# WiFi.net
KiCad netlist of a schematic drawn in EAGLE
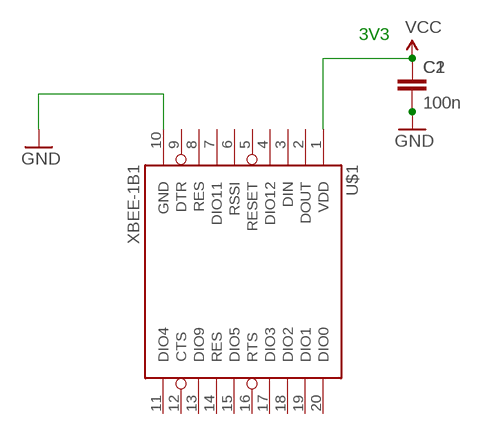
[diagram p0: schematic, sheet 1]

(export (version "E")
  (design (tool "Eeschema 10.0.6"))
  (components
    (comp (ref "C1")
      (value "CAPKIT")
      (footprint "eagle-import:CAP-PTH-SMALL-KIT")
      (libsource (lib "eagle-import") (part "CAPKIT"))
    )
    (comp (ref "C2")
      (value "100n")
      (footprint "eagle-import:CAP-PTH-SMALL-KIT")
      (libsource (lib "eagle-import") (part "CAPKIT"))
    )
    (comp (ref "U$1")
      (value "XBEE-1B1")
      (footprint "eagle-import:XBEE-1")
      (libsource (lib "eagle-import") (part "XBEE-1B1"))
    )
  )
  (nets
    (net (code "1") (name "GND") (class "Default")
      (node (ref "C1") (pin "2") (pinfunction "2_2") (pintype "passive"))
      (node (ref "C2") (pin "2") (pinfunction "2_2") (pintype "passive"))
      (node (ref "U$1") (pin "10") (pinfunction "GND_10") (pintype "power_in"))
    )
    (net (code "2") (name "VCC") (class "Default")
      (node (ref "C1") (pin "1") (pinfunction "1_1") (pintype "passive"))
      (node (ref "C2") (pin "1") (pinfunction "1_1") (pintype "passive"))
      (node (ref "U$1") (pin "1") (pinfunction "VDD_1") (pintype "power_in"))
    )
    (net (code "3") (name "unconnected-(U$1-CTS-Pad12)") (class "Default")
      (node (ref "U$1") (pin "12") (pinfunction "CTS_12") (pintype "output"))
    )
    (net (code "4") (name "unconnected-(U$1-DIN-Pad3)") (class "Default")
      (node (ref "U$1") (pin "3") (pinfunction "DIN_3") (pintype "input"))
    )
    (net (code "5") (name "unconnected-(U$1-DIO0-Pad20)") (class "Default")
      (node (ref "U$1") (pin "20") (pinfunction "DIO0_20") (pintype "bidirectional"))
    )
    (net (code "6") (name "unconnected-(U$1-DIO1-Pad19)") (class "Default")
      (node (ref "U$1") (pin "19") (pinfunction "DIO1_19") (pintype "bidirectional"))
    )
    (net (code "7") (name "unconnected-(U$1-DIO2-Pad18)") (class "Default")
      (node (ref "U$1") (pin "18") (pinfunction "DIO2_18") (pintype "bidirectional"))
    )
    (net (code "8") (name "unconnected-(U$1-DIO3-Pad17)") (class "Default")
      (node (ref "U$1") (pin "17") (pinfunction "DIO3_17") (pintype "bidirectional"))
    )
    (net (code "9") (name "unconnected-(U$1-DIO4-Pad11)") (class "Default")
      (node (ref "U$1") (pin "11") (pinfunction "DIO4_11") (pintype "bidirectional"))
    )
    (net (code "10") (name "unconnected-(U$1-DIO5-Pad15)") (class "Default")
      (node (ref "U$1") (pin "15") (pinfunction "DIO5_15") (pintype "bidirectional"))
    )
    (net (code "11") (name "unconnected-(U$1-DIO9-Pad13)") (class "Default")
      (node (ref "U$1") (pin "13") (pinfunction "DIO9_13") (pintype "bidirectional"))
    )
    (net (code "12") (name "unconnected-(U$1-DIO11-Pad7)") (class "Default")
      (node (ref "U$1") (pin "7") (pinfunction "DIO11_7") (pintype "bidirectional"))
    )
    (net (code "13") (name "unconnected-(U$1-DIO12-Pad4)") (class "Default")
      (node (ref "U$1") (pin "4") (pinfunction "DIO12_4") (pintype "bidirectional"))
    )
    (net (code "14") (name "unconnected-(U$1-DOUT-Pad2)") (class "Default")
      (node (ref "U$1") (pin "2") (pinfunction "DOUT_2") (pintype "output"))
    )
    (net (code "15") (name "unconnected-(U$1-DTR-Pad9)") (class "Default")
      (node (ref "U$1") (pin "9") (pinfunction "DTR_9") (pintype "bidirectional"))
    )
    (net (code "16") (name "unconnected-(U$1-RES-Pad8)") (class "Default")
      (node (ref "U$1") (pin "8") (pinfunction "RES_8") (pintype "bidirectional"))
    )
    (net (code "17") (name "unconnected-(U$1-RES-Pad14)") (class "Default")
      (node (ref "U$1") (pin "14") (pinfunction "RES_14") (pintype "bidirectional"))
    )
    (net (code "18") (name "unconnected-(U$1-RESET-Pad5)") (class "Default")
      (node (ref "U$1") (pin "5") (pinfunction "RESET_5") (pintype "input"))
    )
    (net (code "19") (name "unconnected-(U$1-RSSI-Pad6)") (class "Default")
      (node (ref "U$1") (pin "6") (pinfunction "RSSI_6") (pintype "bidirectional"))
    )
    (net (code "20") (name "unconnected-(U$1-RTS-Pad16)") (class "Default")
      (node (ref "U$1") (pin "16") (pinfunction "RTS_16") (pintype "input"))
    )
  )
)
